# PRUC-Voltmeter_USB-UART-Converter.net
KiCad netlist of a schematic drawn in Altium Designer
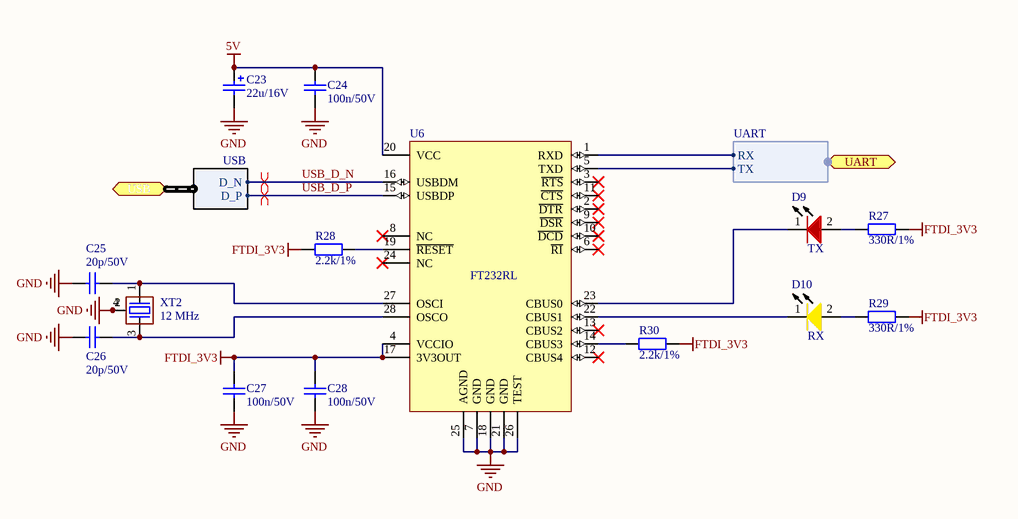
[diagram p0: PRUC-Voltmeter_USB-UART-Converter.SchDoc]

(export (version "E")
  (design (tool "Eeschema 10.0.6"))
  (components
    (comp (ref "C23")
      (value "22u/16V")
      (footprint "Tantalum_B")
      (fields
        (field (name "PART NUMBER") "TAJB226K016R")
        (field (name "MANUFACTURER") "AVX")
        (field (name "MANUFACTURER PART NUMBER") "TAJB226K016RNJ")
      )
      (libsource (lib "private") (part "Cap_Pol"))
    )
    (comp (ref "C24")
      (value "100n/50V")
      (footprint "MLCC_0805")
      (fields (field (name "PART NUMBER") "CL21B104JBCNNNC") (field (name "MANUFACTURER") "Samsung"))
      (libsource (lib "private") (part "Cap"))
    )
    (comp (ref "C25")
      (value "20p/50V")
      (footprint "MLCC_0603")
      (fields (field (name "PART NUMBER") "CL10C200JB8NNNC") (field (name "MANUFACTURER") "Samsung"))
      (libsource (lib "private") (part "Cap"))
    )
    (comp (ref "C26")
      (value "20p/50V")
      (footprint "MLCC_0603")
      (fields (field (name "PART NUMBER") "CL10C200JB8NNNC") (field (name "MANUFACTURER") "Samsung"))
      (libsource (lib "private") (part "Cap"))
    )
    (comp (ref "C27")
      (value "100n/50V")
      (footprint "MLCC_0805")
      (fields (field (name "PART NUMBER") "CL21B104JBCNNNC") (field (name "MANUFACTURER") "Samsung"))
      (libsource (lib "private") (part "Cap"))
    )
    (comp (ref "C28")
      (value "100n/50V")
      (footprint "MLCC_0805")
      (fields (field (name "PART NUMBER") "CL21B104JBCNNNC") (field (name "MANUFACTURER") "Samsung"))
      (libsource (lib "private") (part "Cap"))
    )
    (comp (ref "D9")
      (value "TX")
      (footprint "LED_0805_R")
      (fields (field (name "PART NUMBER") "OSR50805C1E") (field (name "MANUFACTURER") "OptoSupply"))
      (libsource (lib "private") (part "LED_KA_R"))
    )
    (comp (ref "D10")
      (value "RX")
      (footprint "LED_0805_Y")
      (fields (field (name "PART NUMBER") "OSY50805C1E") (field (name "MANUFACTURER") "OptoSupply"))
      (libsource (lib "private") (part "LED_KA_Y"))
    )
    (comp (ref "R27")
      (value "330R/1%")
      (footprint "R_0603")
      (fields (field (name "PART NUMBER") "0603SAF3300T5E") (field (name "MANUFACTURER") "Royalohm"))
      (libsource (lib "") (part "Res_1"))
    )
    (comp (ref "R28")
      (value "2.2k/1%")
      (footprint "R_0603")
      (fields (field (name "PART NUMBER") "0603SAF2201T5E") (field (name "MANUFACTURER") "Royalohm"))
      (libsource (lib "private") (part "Res"))
    )
    (comp (ref "R29")
      (value "330R/1%")
      (footprint "R_0603")
      (fields (field (name "PART NUMBER") "0603SAF3300T5E") (field (name "MANUFACTURER") "Royalohm"))
      (libsource (lib "") (part "Res_1"))
    )
    (comp (ref "R30")
      (value "2.2k/1%")
      (footprint "R_0603")
      (fields (field (name "PART NUMBER") "0603SAF2201T5E") (field (name "MANUFACTURER") "Royalohm"))
      (libsource (lib "") (part "Res_1"))
    )
    (comp (ref "U6")
      (value "FT232RL")
      (footprint "TSSOP-28_M")
      (fields (field (name "MANUFACTURER") "FTDI"))
      (libsource (lib "private") (part "FT232RL"))
    )
    (comp (ref "XT2")
      (value "12 MHz")
      (footprint "ABM3B")
      (fields (field (name "PART NUMBER") "ABM3B-12.000MHZ-B2-T") (field (name "MANUFACTURER") "ABRACON"))
      (libsource (lib "private") (part "RESONATOR_CGCG"))
    )
  )
  (nets
    (net (code "3") (name "/RX") (class "Default")
      (node (ref "U6") (pin "1") (pinfunction "RXD_1") (pintype "bidirectional"))
    )
    (net (code "4") (name "/TX") (class "Default")
      (node (ref "U6") (pin "5") (pinfunction "TXD_5") (pintype "bidirectional"))
    )
    (net (code "5") (name "/USB_D_N") (class "Default")
      (node (ref "U6") (pin "16") (pinfunction "USBDM_16") (pintype "bidirectional"))
    )
    (net (code "6") (name "/USB_D_P") (class "Default")
      (node (ref "U6") (pin "15") (pinfunction "USBDP_15") (pintype "bidirectional"))
    )
    (net (code "9") (name "5V") (class "Default")
      (node (ref "C23") (pin "1") (pinfunction "1_1") (pintype "passive"))
      (node (ref "C24") (pin "1") (pinfunction "1_1") (pintype "passive"))
      (node (ref "U6") (pin "20") (pinfunction "VCC_20") (pintype "power_in"))
    )
    (net (code "10") (name "FTDI_3V3") (class "Default")
      (node (ref "C27") (pin "1") (pinfunction "1_1") (pintype "passive"))
      (node (ref "C28") (pin "1") (pinfunction "1_1") (pintype "passive"))
      (node (ref "R27") (pin "2") (pinfunction "2_2") (pintype "passive"))
      (node (ref "R28") (pin "2") (pinfunction "2_2") (pintype "passive"))
      (node (ref "R29") (pin "2") (pinfunction "2_2") (pintype "passive"))
      (node (ref "R30") (pin "2") (pinfunction "2_2") (pintype "passive"))
      (node (ref "U6") (pin "17") (pinfunction "3V3OUT_17") (pintype "power_in"))
      (node (ref "U6") (pin "4") (pinfunction "VCCIO_4") (pintype "power_in"))
    )
    (net (code "11") (name "GND") (class "Default")
      (node (ref "C23") (pin "2") (pinfunction "2_2") (pintype "passive"))
      (node (ref "C24") (pin "2") (pinfunction "2_2") (pintype "passive"))
      (node (ref "C25") (pin "1") (pinfunction "1_1") (pintype "passive"))
      (node (ref "C26") (pin "1") (pinfunction "1_1") (pintype "passive"))
      (node (ref "C27") (pin "2") (pinfunction "2_2") (pintype "passive"))
      (node (ref "C28") (pin "2") (pinfunction "2_2") (pintype "passive"))
      (node (ref "U6") (pin "18") (pinfunction "GND_18") (pintype "power_in"))
      (node (ref "U6") (pin "21") (pinfunction "GND_21") (pintype "power_in"))
      (node (ref "U6") (pin "25") (pinfunction "AGND_25") (pintype "power_in"))
      (node (ref "U6") (pin "26") (pinfunction "TEST_26") (pintype "passive"))
      (node (ref "U6") (pin "7") (pinfunction "GND_7") (pintype "power_in"))
      (node (ref "XT2") (pin "2") (pinfunction "GND_2") (pintype "passive"))
      (node (ref "XT2") (pin "4") (pinfunction "GND_4") (pintype "passive"))
    )
    (net (code "12") (name "Net-(D9-A)") (class "Default")
      (node (ref "D9") (pin "2") (pinfunction "A_2") (pintype "passive"))
      (node (ref "R27") (pin "1") (pinfunction "1_1") (pintype "passive"))
    )
    (net (code "13") (name "Net-(D9-K)") (class "Default")
      (node (ref "D9") (pin "1") (pinfunction "K_1") (pintype "passive"))
      (node (ref "U6") (pin "23") (pinfunction "CBUS0_23") (pintype "bidirectional"))
    )
    (net (code "14") (name "Net-(D10-A)") (class "Default")
      (node (ref "D10") (pin "2") (pinfunction "A_2") (pintype "passive"))
      (node (ref "R29") (pin "1") (pinfunction "1_1") (pintype "passive"))
    )
    (net (code "15") (name "Net-(D10-K)") (class "Default")
      (node (ref "D10") (pin "1") (pinfunction "K_1") (pintype "passive"))
      (node (ref "U6") (pin "22") (pinfunction "CBUS1_22") (pintype "bidirectional"))
    )
    (net (code "16") (name "Net-(U6-CBUS3)") (class "Default")
      (node (ref "R30") (pin "1") (pinfunction "1_1") (pintype "passive"))
      (node (ref "U6") (pin "14") (pinfunction "CBUS3_14") (pintype "bidirectional"))
    )
    (net (code "17") (name "Net-(U6-OSCI)") (class "Default")
      (node (ref "C25") (pin "2") (pinfunction "2_2") (pintype "passive"))
      (node (ref "U6") (pin "27") (pinfunction "OSCI_27") (pintype "passive"))
      (node (ref "XT2") (pin "1") (pinfunction "inp_1") (pintype "passive"))
    )
    (net (code "18") (name "Net-(U6-OSCO)") (class "Default")
      (node (ref "C26") (pin "2") (pinfunction "2_2") (pintype "passive"))
      (node (ref "U6") (pin "28") (pinfunction "OSCO_28") (pintype "passive"))
      (node (ref "XT2") (pin "3") (pinfunction "out_3") (pintype "passive"))
    )
    (net (code "19") (name "Net-(U6-~{RESET})") (class "Default")
      (node (ref "R28") (pin "1") (pinfunction "1_1") (pintype "passive"))
      (node (ref "U6") (pin "19") (pinfunction "~{RESET}_19") (pintype "passive"))
    )
    (net (code "20") (name "unconnected-(U6-CBUS2-Pad13)") (class "Default")
      (node (ref "U6") (pin "13") (pinfunction "CBUS2_13") (pintype "bidirectional+no_connect"))
    )
    (net (code "21") (name "unconnected-(U6-CBUS4-Pad12)") (class "Default")
      (node (ref "U6") (pin "12") (pinfunction "CBUS4_12") (pintype "bidirectional+no_connect"))
    )
    (net (code "22") (name "unconnected-(U6-NC-Pad8)") (class "Default")
      (node (ref "U6") (pin "8") (pinfunction "NC_8") (pintype "passive+no_connect"))
    )
    (net (code "23") (name "unconnected-(U6-NC-Pad24)") (class "Default")
      (node (ref "U6") (pin "24") (pinfunction "NC_24") (pintype "passive+no_connect"))
    )
    (net (code "24") (name "unconnected-(U6-~{CTS}-Pad11)") (class "Default")
      (node (ref "U6") (pin "11") (pinfunction "~{CTS}_11") (pintype "bidirectional+no_connect"))
    )
    (net (code "25") (name "unconnected-(U6-~{DCD}-Pad10)") (class "Default")
      (node (ref "U6") (pin "10") (pinfunction "~{DCD}_10") (pintype "bidirectional+no_connect"))
    )
    (net (code "26") (name "unconnected-(U6-~{DSR}-Pad9)") (class "Default")
      (node (ref "U6") (pin "9") (pinfunction "~{DSR}_9") (pintype "bidirectional+no_connect"))
    )
    (net (code "27") (name "unconnected-(U6-~{DTR}-Pad2)") (class "Default")
      (node (ref "U6") (pin "2") (pinfunction "~{DTR}_2") (pintype "bidirectional+no_connect"))
    )
    (net (code "28") (name "unconnected-(U6-~{RI}-Pad6)") (class "Default")
      (node (ref "U6") (pin "6") (pinfunction "~{RI}_6") (pintype "bidirectional+no_connect"))
    )
    (net (code "29") (name "unconnected-(U6-~{RTS}-Pad3)") (class "Default")
      (node (ref "U6") (pin "3") (pinfunction "~{RTS}_3") (pintype "bidirectional+no_connect"))
    )
  )
)
